# USB_HUB_2_0.net
KiCad netlist of a schematic drawn in Altium Designer
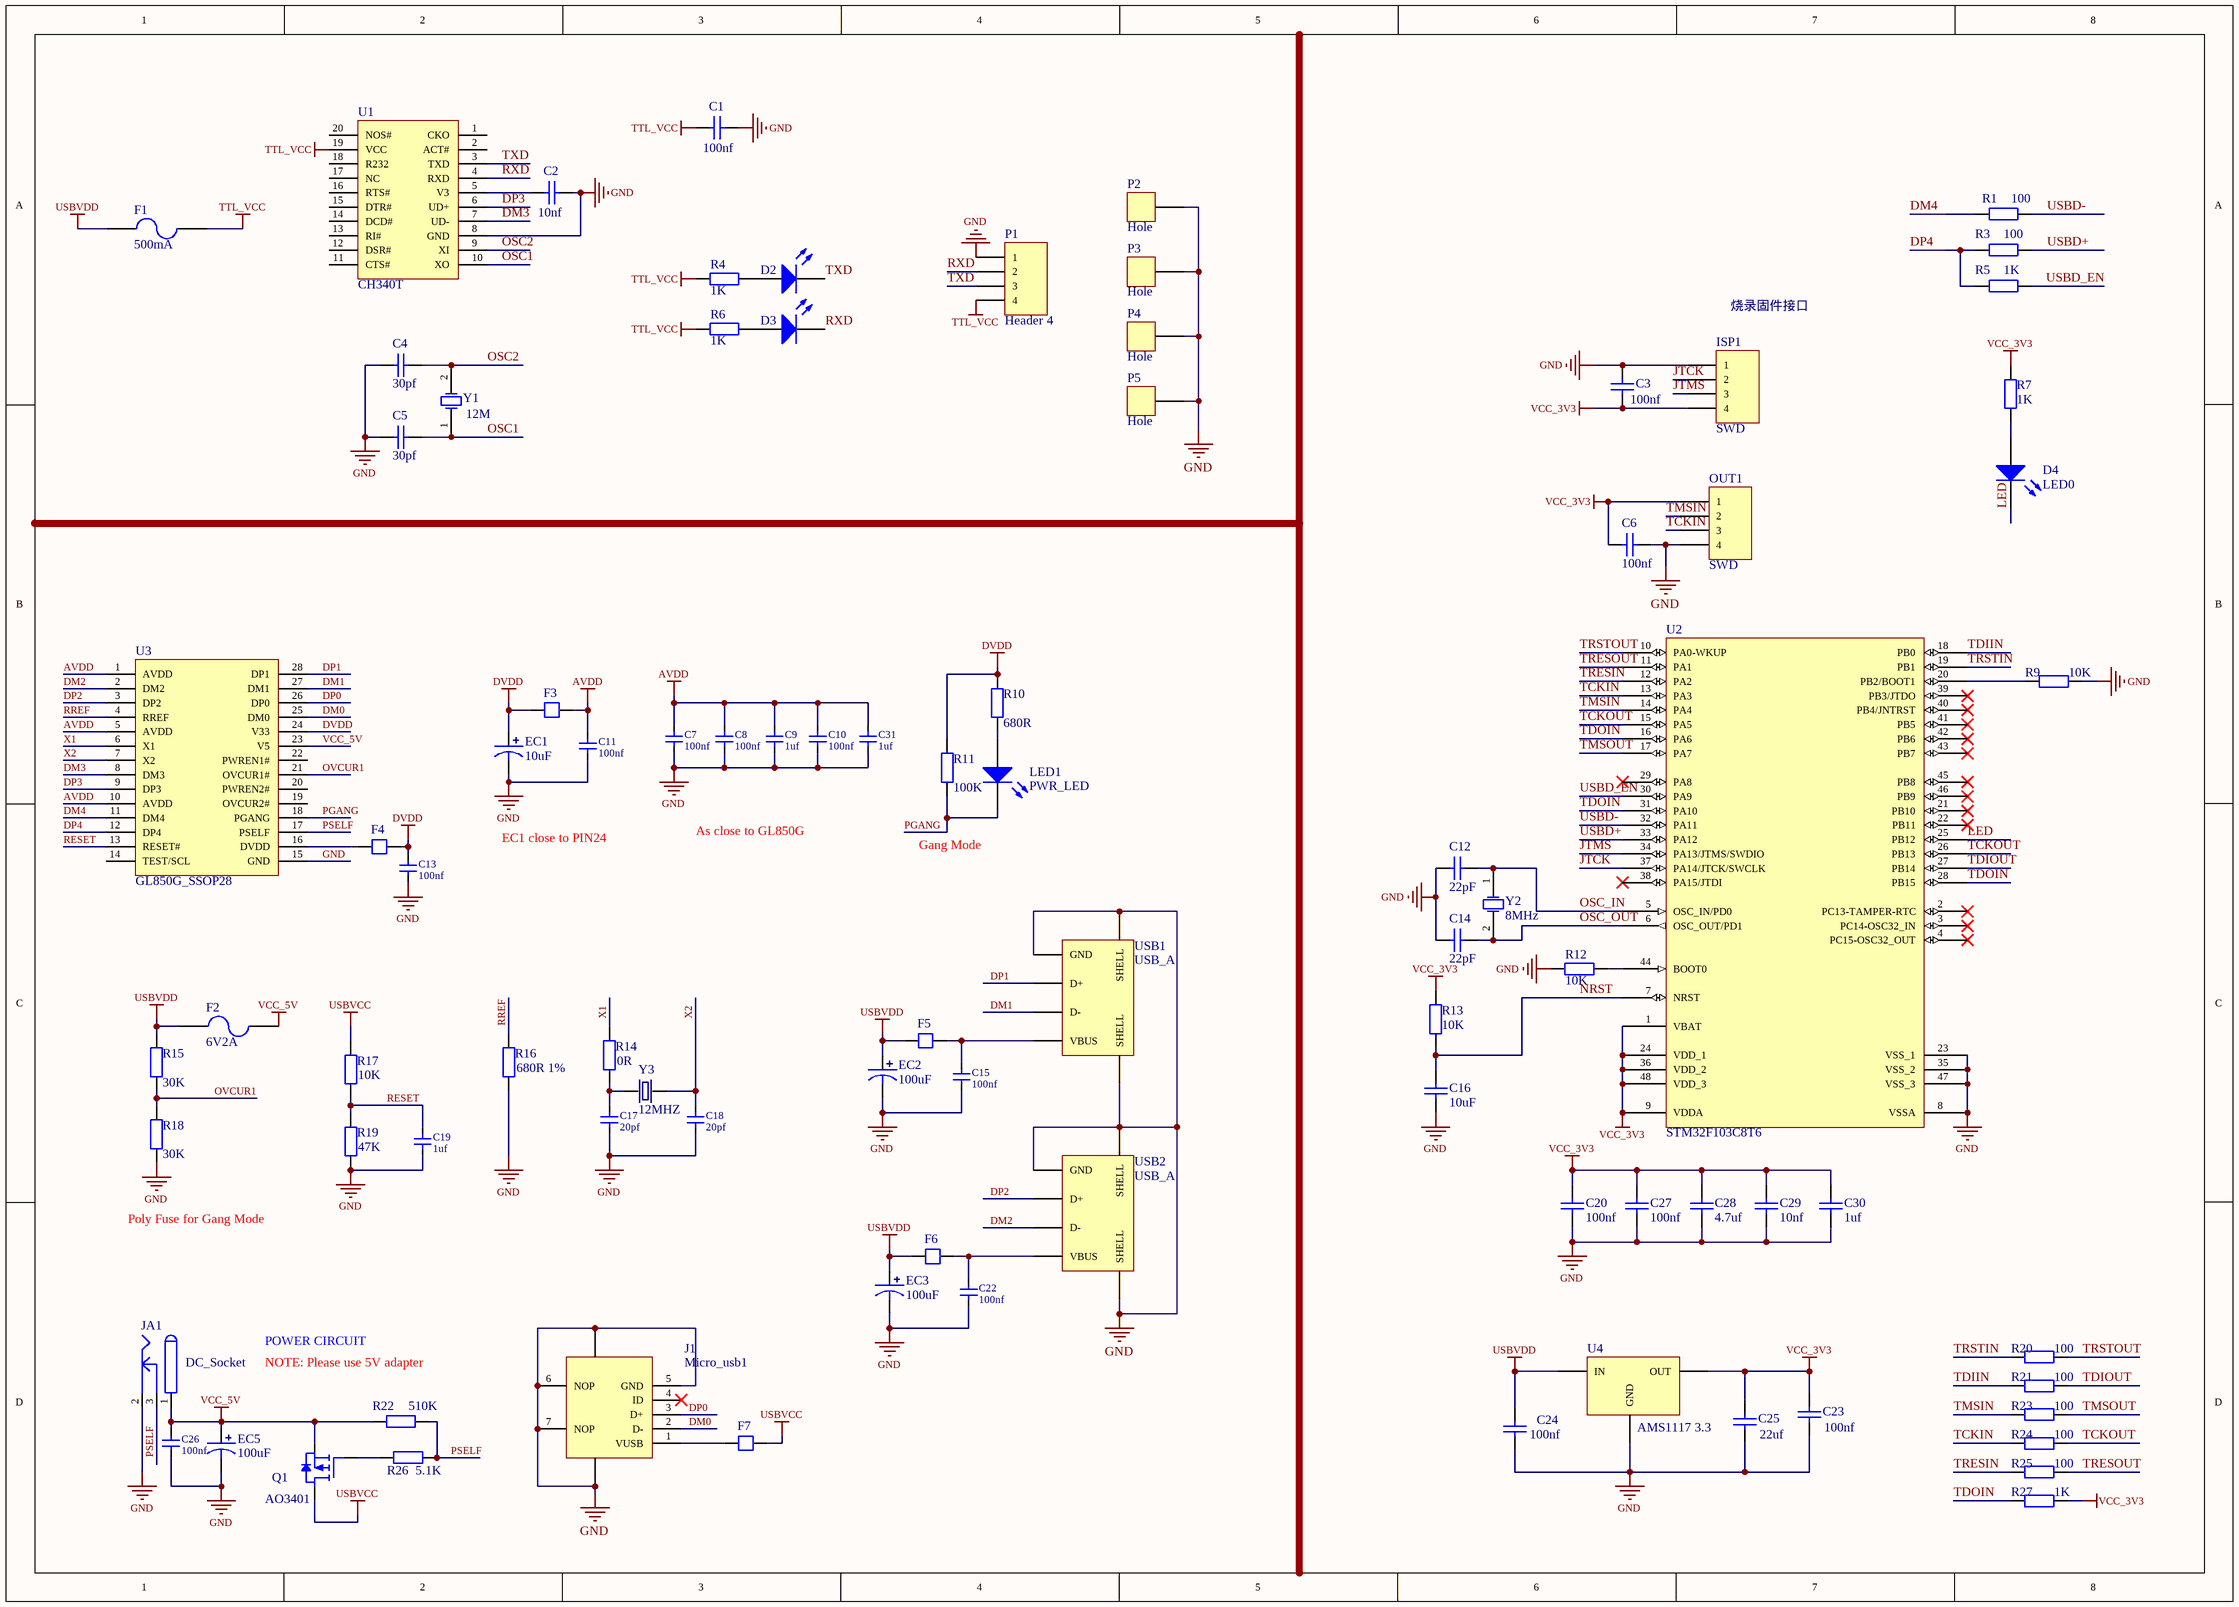
[diagram p0: USB HUB 2.0.SchDoc]

(export (version "E")
  (design (tool "Eeschema 10.0.6"))
  (components
    (comp (ref "C1")
      (value "100nf")
      (footprint "j1-0603")
      (description "Capacitor")
      (fields (field (name "Comment") "Cap") (field (name "PUBLISHER") "Altium Limited"))
      (libsource (lib "Miscellaneous Devices") (part "Cap"))
    )
    (comp (ref "C2")
      (value "10nf")
      (footprint "j1-0603")
      (description "Capacitor")
      (fields (field (name "Comment") "Cap") (field (name "PUBLISHER") "Altium Limited"))
      (libsource (lib "Miscellaneous Devices") (part "Cap"))
    )
    (comp (ref "C3")
      (value "100nf")
      (footprint "j1-0603")
      (description "Capacitor")
      (fields (field (name "PUBLISHER") "Altium Limited"))
      (libsource (lib "Miscellaneous Devices") (part "Cap"))
    )
    (comp (ref "C4")
      (value "30pf")
      (footprint "j1-0603")
      (description "Capacitor")
      (fields (field (name "Comment") "Cap") (field (name "PUBLISHER") "Altium Limited"))
      (libsource (lib "Miscellaneous Devices") (part "Cap"))
    )
    (comp (ref "C5")
      (value "30pf")
      (footprint "j1-0603")
      (description "Capacitor")
      (fields (field (name "Comment") "Cap") (field (name "PUBLISHER") "Altium Limited"))
      (libsource (lib "Miscellaneous Devices") (part "Cap"))
    )
    (comp (ref "C6")
      (value "100nf")
      (footprint "j1-0603")
      (description "Capacitor")
      (fields (field (name "PUBLISHER") "Altium Limited"))
      (libsource (lib "Miscellaneous Devices") (part "Cap"))
    )
    (comp (ref "C7")
      (value "100nf")
      (footprint "j1-0603")
      (description "Capacitor")
      (libsource (lib "Miscellaneous Devices") (part "CAP"))
    )
    (comp (ref "C8")
      (value "100nf")
      (footprint "j1-0603")
      (description "Capacitor")
      (libsource (lib "Miscellaneous Devices") (part "CAP"))
    )
    (comp (ref "C9")
      (value "1uf")
      (footprint "j1-0603")
      (description "Capacitor")
      (libsource (lib "Miscellaneous Devices") (part "CAP"))
    )
    (comp (ref "C10")
      (value "100nf")
      (footprint "j1-0603")
      (description "Capacitor")
      (libsource (lib "Miscellaneous Devices") (part "CAP"))
    )
    (comp (ref "C11")
      (value "100nf")
      (footprint "j1-0603")
      (description "Capacitor")
      (libsource (lib "Miscellaneous Devices") (part "CAP"))
    )
    (comp (ref "C12")
      (value "22pF")
      (footprint "j1-0603")
      (description "Capacitor")
      (fields (field (name "PUBLISHER") "Altium Limited"))
      (libsource (lib "Miscellaneous Devices") (part "Cap"))
    )
    (comp (ref "C13")
      (value "100nf")
      (footprint "j1-0603")
      (description "Capacitor")
      (libsource (lib "Miscellaneous Devices") (part "CAP"))
    )
    (comp (ref "C14")
      (value "22pF")
      (footprint "j1-0603")
      (description "Capacitor")
      (fields (field (name "PUBLISHER") "Altium Limited"))
      (libsource (lib "Miscellaneous Devices") (part "Cap"))
    )
    (comp (ref "C15")
      (value "100nf")
      (footprint "j1-0603")
      (description "Capacitor")
      (libsource (lib "Miscellaneous Devices") (part "CAP"))
    )
    (comp (ref "C16")
      (value "10uF")
      (footprint "j1-0603")
      (description "Capacitor")
      (fields (field (name "PUBLISHER") "Altium Limited"))
      (libsource (lib "Miscellaneous Devices") (part "Cap"))
    )
    (comp (ref "C17")
      (value "20pf")
      (footprint "j1-0603")
      (description "Capacitor")
      (libsource (lib "Miscellaneous Devices") (part "CAP"))
    )
    (comp (ref "C18")
      (value "20pf")
      (footprint "j1-0603")
      (description "Capacitor")
      (libsource (lib "Miscellaneous Devices") (part "CAP"))
    )
    (comp (ref "C19")
      (value "1uf")
      (footprint "j1-0603")
      (description "Capacitor")
      (libsource (lib "Miscellaneous Devices") (part "CAP"))
    )
    (comp (ref "C20")
      (value "100nf")
      (footprint "j1-0603")
      (description "Capacitor")
      (fields (field (name "PUBLISHER") "Altium Limited"))
      (libsource (lib "Miscellaneous Devices") (part "Cap"))
    )
    (comp (ref "C22")
      (value "100nf")
      (footprint "j1-0603")
      (description "Capacitor")
      (libsource (lib "Miscellaneous Devices") (part "CAP"))
    )
    (comp (ref "C23")
      (value "100nf")
      (footprint "j1-0603")
      (description "Capacitor")
      (fields (field (name "PUBLISHER") "Altium Limited"))
      (libsource (lib "Miscellaneous Devices") (part "Cap"))
    )
    (comp (ref "C24")
      (value "100nf")
      (footprint "j1-0603")
      (description "Capacitor")
      (fields (field (name "PUBLISHER") "Altium Limited"))
      (libsource (lib "Miscellaneous Devices") (part "Cap"))
    )
    (comp (ref "C25")
      (value "22uf")
      (footprint "j1-0603")
      (description "Capacitor")
      (fields (field (name "PUBLISHER") "Altium Limited"))
      (libsource (lib "Miscellaneous Devices") (part "Cap"))
    )
    (comp (ref "C26")
      (value "100nf")
      (footprint "j1-0603")
      (description "Capacitor")
      (libsource (lib "Miscellaneous Devices") (part "CAP"))
    )
    (comp (ref "C27")
      (value "100nf")
      (footprint "j1-0603")
      (description "Capacitor")
      (fields (field (name "PUBLISHER") "Altium Limited"))
      (libsource (lib "Miscellaneous Devices") (part "Cap"))
    )
    (comp (ref "C28")
      (value "4.7uf")
      (footprint "j1-0603")
      (description "Capacitor")
      (fields (field (name "PUBLISHER") "Altium Limited"))
      (libsource (lib "Miscellaneous Devices") (part "Cap"))
    )
    (comp (ref "C29")
      (value "10nf")
      (footprint "j1-0603")
      (description "Capacitor")
      (fields (field (name "PUBLISHER") "Altium Limited"))
      (libsource (lib "Miscellaneous Devices") (part "Cap"))
    )
    (comp (ref "C30")
      (value "1uf")
      (footprint "j1-0603")
      (description "Capacitor")
      (fields (field (name "PUBLISHER") "Altium Limited"))
      (libsource (lib "Miscellaneous Devices") (part "Cap"))
    )
    (comp (ref "C31")
      (value "1uf")
      (footprint "j1-0603")
      (description "Capacitor")
      (libsource (lib "Miscellaneous Devices") (part "CAP"))
    )
    (comp (ref "D2")
      (value "LED")
      (footprint "j1-0603")
      (description "Typical INFRARED GaAs LED")
      (fields (field (name "PUBLISHER") "Altium Limited"))
      (libsource (lib "Miscellaneous Devices") (part "LED0"))
    )
    (comp (ref "D3")
      (value "LED")
      (footprint "j1-0603")
      (description "Typical INFRARED GaAs LED")
      (fields (field (name "PUBLISHER") "Altium Limited"))
      (libsource (lib "Miscellaneous Devices") (part "LED0"))
    )
    (comp (ref "D4")
      (value "LED0")
      (footprint "j1-0603")
      (description "Typical INFRARED GaAs LED")
      (fields (field (name "PUBLISHER") "Altium Limited"))
      (libsource (lib "Miscellaneous Devices") (part "LED0"))
    )
    (comp (ref "EC1")
      (value "10uF")
      (footprint "6-0805_L")
      (description "贴片电解电容")
      (libsource (lib "电容") (part "SMD_ECAP"))
    )
    (comp (ref "EC2")
      (value "100uF")
      (footprint "SMD-EC5.0X5.3X5.4")
      (description "贴片电解电容")
      (libsource (lib "电容") (part "SMD_ECAP"))
    )
    (comp (ref "EC3")
      (value "100uF")
      (footprint "SMD-EC5.0X5.3X5.4")
      (description "贴片电解电容")
      (libsource (lib "电容") (part "SMD_ECAP"))
    )
    (comp (ref "EC5")
      (value "100uF")
      (footprint "SMD-EC5.0X5.3X5.4")
      (description "贴片电解电容")
      (libsource (lib "电容") (part "SMD_ECAP"))
    )
    (comp (ref "F1")
      (value "500mA")
      (footprint "1812C")
      (description "Fuse")
      (fields (field (name "PUBLISHER") "Altium Limited"))
      (libsource (lib "Miscellaneous Devices") (part "Fuse 2"))
    )
    (comp (ref "F2")
      (value "6V2A")
      (footprint "1812")
      (description "Fuse")
      (fields (field (name "PUBLISHER") "Altium Limited"))
      (libsource (lib "Miscellaneous Devices") (part "Fuse 2"))
    )
    (comp (ref "F3") (value "FB") (footprint "6-0805_L") (libsource (lib "haoxaingyin") (part "FB")))
    (comp (ref "F4") (value "FB") (footprint "6-0805_L") (libsource (lib "haoxaingyin") (part "FB")))
    (comp (ref "F5") (value "FB") (footprint "6-0805_L") (libsource (lib "haoxaingyin") (part "FB")))
    (comp (ref "F6") (value "FB") (footprint "6-0805_L") (libsource (lib "haoxaingyin") (part "FB")))
    (comp (ref "F7") (value "FB") (footprint "6-0805_L") (libsource (lib "haoxaingyin") (part "FB")))
    (comp (ref "ISP1")
      (value "SWD")
      (footprint "HDR1X4")
      (description "Header, 4-Pin")
      (fields (field (name "PUBLISHER") "Altium Limited"))
      (libsource (lib "Miscellaneous Connectors") (part "Header 4"))
    )
    (comp (ref "J1")
      (value "Micro_usb1")
      (footprint "Micro_USB1")
      (libsource (lib "haoxaingyin") (part "Micro_usb1"))
    )
    (comp (ref "JA1") (value "DC_Socket") (footprint "DC-002") (libsource (lib "电源插座") (part "DC_Socket")))
    (comp (ref "LED1")
      (value "PWR_LED")
      (footprint "j1-0603")
      (description "Typical INFRARED GaAs LED")
      (fields (field (name "PUBLISHER") "Altium Limited"))
      (libsource (lib "Miscellaneous Devices") (part "LED0"))
    )
    (comp (ref "OUT1")
      (value "SWD")
      (footprint "HDR1X4")
      (description "Header, 4-Pin")
      (fields (field (name "PUBLISHER") "Altium Limited"))
      (libsource (lib "Miscellaneous Connectors") (part "Header 4"))
    )
    (comp (ref "P1")
      (value "Header 4")
      (footprint "HDR1X4")
      (description "Header, 4-Pin")
      (fields (field (name "PUBLISHER") "Altium Limited"))
      (libsource (lib "Connectors") (part "Header 4"))
    )
    (comp (ref "P2") (value "Hole") (footprint "Hole") (libsource (lib "haoxaingyin") (part "Hole")))
    (comp (ref "P3") (value "Hole") (footprint "Hole") (libsource (lib "haoxaingyin") (part "Hole")))
    (comp (ref "P4") (value "Hole") (footprint "Hole") (libsource (lib "haoxaingyin") (part "Hole")))
    (comp (ref "P5") (value "Hole") (footprint "Hole") (libsource (lib "haoxaingyin") (part "Hole")))
    (comp (ref "Q1")
      (value "AO3401")
      (footprint "SOT-23")
      (description "P-Channel MOSFET")
      (libsource (lib "Miscellaneous Devices") (part "MOSFET-P"))
    )
    (comp (ref "R1")
      (value "100")
      (footprint "j1-0603")
      (description "Resistor")
      (fields (field (name "PUBLISHER") "Altium Limited"))
      (libsource (lib "") (part "Res2_1"))
    )
    (comp (ref "R3")
      (value "100")
      (footprint "j1-0603")
      (description "Resistor")
      (fields (field (name "PUBLISHER") "Altium Limited"))
      (libsource (lib "") (part "Res2_1"))
    )
    (comp (ref "R4")
      (value "1K")
      (footprint "j1-0603")
      (description "Resistor")
      (fields (field (name "Comment") "Res2") (field (name "PUBLISHER") "Altium Limited"))
      (libsource (lib "") (part "Res2_1"))
    )
    (comp (ref "R5")
      (value "1K")
      (footprint "j1-0603")
      (description "Resistor")
      (fields (field (name "PUBLISHER") "Altium Limited"))
      (libsource (lib "") (part "Res2_1"))
    )
    (comp (ref "R6")
      (value "1K")
      (footprint "j1-0603")
      (description "Resistor")
      (fields (field (name "Comment") "Res2") (field (name "PUBLISHER") "Altium Limited"))
      (libsource (lib "") (part "Res2_1"))
    )
    (comp (ref "R7")
      (value "1K")
      (footprint "j1-0603")
      (description "Resistor")
      (fields (field (name "PUBLISHER") "Altium Limited"))
      (libsource (lib "Miscellaneous Devices") (part "Res2"))
    )
    (comp (ref "R9")
      (value "10K")
      (footprint "j1-0603")
      (description "Resistor")
      (fields (field (name "PUBLISHER") "Altium Limited"))
      (libsource (lib "") (part "Res2_1"))
    )
    (comp (ref "R10")
      (value "680R")
      (footprint "j1-0603")
      (description "Resistor")
      (fields (field (name "PUBLISHER") "Altium Limited"))
      (libsource (lib "Miscellaneous Devices") (part "Res2"))
    )
    (comp (ref "R11")
      (value "100K")
      (footprint "j1-0603")
      (description "Resistor")
      (fields (field (name "PUBLISHER") "Altium Limited"))
      (libsource (lib "Miscellaneous Devices") (part "Res2"))
    )
    (comp (ref "R12")
      (value "10K")
      (footprint "j1-0603")
      (description "Resistor")
      (fields (field (name "PUBLISHER") "Altium Limited"))
      (libsource (lib "") (part "Res2_1"))
    )
    (comp (ref "R13")
      (value "10K")
      (footprint "j1-0603")
      (description "Resistor")
      (fields (field (name "PUBLISHER") "Altium Limited"))
      (libsource (lib "Miscellaneous Devices") (part "Res2"))
    )
    (comp (ref "R14")
      (value "0R")
      (footprint "j1-0603")
      (description "Resistor")
      (fields (field (name "PUBLISHER") "Altium Limited"))
      (libsource (lib "Miscellaneous Devices") (part "Res2"))
    )
    (comp (ref "R15")
      (value "30K")
      (footprint "j1-0603")
      (description "Resistor")
      (fields (field (name "PUBLISHER") "Altium Limited"))
      (libsource (lib "Miscellaneous Devices") (part "Res2"))
    )
    (comp (ref "R16")
      (value "680R 1%")
      (footprint "j1-0603")
      (description "Resistor")
      (fields (field (name "PUBLISHER") "Altium Limited"))
      (libsource (lib "Miscellaneous Devices") (part "Res2"))
    )
    (comp (ref "R17")
      (value "10K")
      (footprint "j1-0603")
      (description "Resistor")
      (fields (field (name "PUBLISHER") "Altium Limited"))
      (libsource (lib "Miscellaneous Devices") (part "Res2"))
    )
    (comp (ref "R18")
      (value "30K")
      (footprint "j1-0603")
      (description "Resistor")
      (fields (field (name "PUBLISHER") "Altium Limited"))
      (libsource (lib "Miscellaneous Devices") (part "Res2"))
    )
    (comp (ref "R19")
      (value "47K")
      (footprint "j1-0603")
      (description "Resistor")
      (fields (field (name "PUBLISHER") "Altium Limited"))
      (libsource (lib "Miscellaneous Devices") (part "Res2"))
    )
    (comp (ref "R20")
      (value "100")
      (footprint "j1-0603")
      (description "Resistor")
      (fields (field (name "PUBLISHER") "Altium Limited"))
      (libsource (lib "") (part "Res2_1"))
    )
    (comp (ref "R21")
      (value "100")
      (footprint "j1-0603")
      (description "Resistor")
      (fields (field (name "PUBLISHER") "Altium Limited"))
      (libsource (lib "") (part "Res2_1"))
    )
    (comp (ref "R22")
      (value "510K")
      (footprint "j1-0603")
      (description "Resistor")
      (fields (field (name "PUBLISHER") "Altium Limited"))
      (libsource (lib "") (part "Res2_2"))
    )
    (comp (ref "R23")
      (value "100")
      (footprint "j1-0603")
      (description "Resistor")
      (fields (field (name "PUBLISHER") "Altium Limited"))
      (libsource (lib "") (part "Res2_1"))
    )
    (comp (ref "R24")
      (value "100")
      (footprint "j1-0603")
      (description "Resistor")
      (fields (field (name "PUBLISHER") "Altium Limited"))
      (libsource (lib "") (part "Res2_1"))
    )
    (comp (ref "R25")
      (value "100")
      (footprint "j1-0603")
      (description "Resistor")
      (fields (field (name "PUBLISHER") "Altium Limited"))
      (libsource (lib "") (part "Res2_1"))
    )
    (comp (ref "R26")
      (value "5.1K")
      (footprint "j1-0603")
      (description "Resistor")
      (fields (field (name "PUBLISHER") "Altium Limited"))
      (libsource (lib "") (part "Res2_1"))
    )
    (comp (ref "R27")
      (value "1K")
      (footprint "j1-0603")
      (description "Resistor")
      (fields (field (name "PUBLISHER") "Altium Limited"))
      (libsource (lib "") (part "Res2_1"))
    )
    (comp (ref "U1") (value "CH340T") (footprint "SSOP20") (libsource (lib "haoxaingyin") (part "CH340T")))
    (comp (ref "U2")
      (value "STM32F103C8T6")
      (footprint "LQFP48 7X7")
      (libsource (lib "STM32系列") (part "STM32F103C8T6"))
    )
    (comp (ref "U3")
      (value "GL850G_SSOP28")
      (footprint "SSOP28")
      (libsource (lib "haoxaingyin") (part "GL850G_SSOP28"))
    )
    (comp (ref "U4")
      (value "AMS1117 3.3")
      (footprint "SOT-223")
      (libsource (lib "Common Power") (part "ASM1117"))
    )
    (comp (ref "USB1") (value "USB_A") (footprint "USB_DIP") (libsource (lib "haoxaingyin") (part "USB_A")))
    (comp (ref "USB2") (value "USB_A") (footprint "USB_DIP") (libsource (lib "haoxaingyin") (part "USB_A")))
    (comp (ref "Y1")
      (value "12M")
      (footprint "HC-49/U-S")
      (description "Crystal Oscillator")
      (fields (field (name "PUBLISHER") "Altium Limited"))
      (libsource (lib "Common Device") (part "XTAL"))
    )
    (comp (ref "Y2")
      (value "8MHz")
      (footprint "HC-49/U-S")
      (description "Crystal Oscillator")
      (fields (field (name "PUBLISHER") "Altium Limited"))
      (libsource (lib "Miscellaneous Devices") (part "XTAL"))
    )
    (comp (ref "Y3") (value "12MHZ") (footprint "HC-49/U-S") (libsource (lib "Common Device") (part "Xtal")))
  )
  (nets
    (net (code "1") (name "/DM0") (class "Default")
      (node (ref "J1") (pin "2") (pinfunction "D-_2") (pintype "passive"))
      (node (ref "U3") (pin "25") (pinfunction "DM0_25") (pintype "passive"))
    )
    (net (code "2") (name "/DM1") (class "Default")
      (node (ref "U3") (pin "27") (pinfunction "DM1_27") (pintype "passive"))
      (node (ref "USB1") (pin "2") (pinfunction "D-_2") (pintype "passive"))
    )
    (net (code "3") (name "/DM2") (class "Default")
      (node (ref "U3") (pin "2") (pinfunction "DM2_2") (pintype "passive"))
      (node (ref "USB2") (pin "2") (pinfunction "D-_2") (pintype "passive"))
    )
    (net (code "4") (name "/DM3") (class "Default")
      (node (ref "U1") (pin "7") (pinfunction "UD-_7") (pintype "passive"))
      (node (ref "U3") (pin "8") (pinfunction "DM3_8") (pintype "passive"))
    )
    (net (code "5") (name "/DM4") (class "Default")
      (node (ref "R1") (pin "1") (pinfunction "1_1") (pintype "passive"))
      (node (ref "U3") (pin "11") (pinfunction "DM4_11") (pintype "passive"))
    )
    (net (code "6") (name "/DP0") (class "Default")
      (node (ref "J1") (pin "3") (pinfunction "D+_3") (pintype "passive"))
      (node (ref "U3") (pin "26") (pinfunction "DP0_26") (pintype "passive"))
    )
    (net (code "7") (name "/DP1") (class "Default")
      (node (ref "U3") (pin "28") (pinfunction "DP1_28") (pintype "passive"))
      (node (ref "USB1") (pin "3") (pinfunction "D+_3") (pintype "passive"))
    )
    (net (code "8") (name "/DP2") (class "Default")
      (node (ref "U3") (pin "3") (pinfunction "DP2_3") (pintype "passive"))
      (node (ref "USB2") (pin "3") (pinfunction "D+_3") (pintype "passive"))
    )
    (net (code "9") (name "/DP3") (class "Default")
      (node (ref "U1") (pin "6") (pinfunction "UD+_6") (pintype "passive"))
      (node (ref "U3") (pin "9") (pinfunction "DP3_9") (pintype "passive"))
    )
    (net (code "10") (name "/DP4") (class "Default")
      (node (ref "R3") (pin "1") (pinfunction "1_1") (pintype "passive"))
      (node (ref "R5") (pin "1") (pinfunction "1_1") (pintype "passive"))
      (node (ref "U3") (pin "12") (pinfunction "DP4_12") (pintype "passive"))
    )
    (net (code "11") (name "/JTCK") (class "Default")
      (node (ref "ISP1") (pin "2") (pinfunction "2_2") (pintype "passive"))
      (node (ref "U2") (pin "37") (pinfunction "PA14/JTCK/SWCLK_37") (pintype "bidirectional"))
    )
    (net (code "12") (name "/JTMS") (class "Default")
      (node (ref "ISP1") (pin "3") (pinfunction "3_3") (pintype "passive"))
      (node (ref "U2") (pin "34") (pinfunction "PA13/JTMS/SWDIO_34") (pintype "bidirectional"))
    )
    (net (code "13") (name "/LED") (class "Default")
      (node (ref "D4") (pin "2") (pinfunction "2_2") (pintype "passive"))
      (node (ref "U2") (pin "25") (pinfunction "PB12_25") (pintype "bidirectional"))
    )
    (net (code "14") (name "/NRST") (class "Default")
      (node (ref "C16") (pin "1") (pinfunction "1_1") (pintype "passive"))
      (node (ref "R13") (pin "1") (pinfunction "1_1") (pintype "passive"))
      (node (ref "U2") (pin "7") (pinfunction "NRST_7") (pintype "bidirectional"))
    )
    (net (code "15") (name "/OSC1") (class "Default")
      (node (ref "C5") (pin "1") (pinfunction "1_1") (pintype "passive"))
      (node (ref "U1") (pin "10") (pinfunction "XO_10") (pintype "passive"))
      (node (ref "Y1") (pin "1") (pinfunction "OSC1_1") (pintype "passive"))
    )
    (net (code "16") (name "/OSC2") (class "Default")
      (node (ref "C4") (pin "1") (pinfunction "1_1") (pintype "passive"))
      (node (ref "U1") (pin "9") (pinfunction "XI_9") (pintype "passive"))
      (node (ref "Y1") (pin "2") (pinfunction "OSC2_2") (pintype "passive"))
    )
    (net (code "17") (name "/OSC_IN") (class "Default")
      (node (ref "C12") (pin "1") (pinfunction "1_1") (pintype "passive"))
      (node (ref "U2") (pin "5") (pinfunction "OSC_IN/PD0_5") (pintype "input"))
      (node (ref "Y2") (pin "1") (pinfunction "OSC1_1") (pintype "passive"))
    )
    (net (code "18") (name "/OSC_OUT") (class "Default")
      (node (ref "C14") (pin "1") (pinfunction "1_1") (pintype "passive"))
      (node (ref "U2") (pin "6") (pinfunction "OSC_OUT/PD1_6") (pintype "output"))
      (node (ref "Y2") (pin "2") (pinfunction "OSC2_2") (pintype "passive"))
    )
    (net (code "19") (name "/OVCUR1") (class "Default")
      (node (ref "R15") (pin "1") (pinfunction "1_1") (pintype "passive"))
      (node (ref "R18") (pin "2") (pinfunction "2_2") (pintype "passive"))
      (node (ref "U3") (pin "21") (pinfunction "OVCUR1#_21") (pintype "passive"))
    )
    (net (code "20") (name "/PGANG") (class "Default")
      (node (ref "LED1") (pin "2") (pinfunction "2_2") (pintype "passive"))
      (node (ref "R11") (pin "1") (pinfunction "1_1") (pintype "passive"))
      (node (ref "U3") (pin "18") (pinfunction "PGANG_18") (pintype "passive"))
    )
    (net (code "21") (name "/PSELF") (class "Default")
      (node (ref "JA1") (pin "3") (pinfunction "3_3") (pintype "power_in"))
      (node (ref "R22") (pin "1") (pinfunction "1_1") (pintype "passive"))
      (node (ref "R26") (pin "2") (pinfunction "2_2") (pintype "passive"))
      (node (ref "U3") (pin "17") (pinfunction "PSELF_17") (pintype "passive"))
    )
    (net (code "22") (name "/RESET") (class "Default")
      (node (ref "C19") (pin "2") (pinfunction "2_2") (pintype "passive"))
      (node (ref "R17") (pin "1") (pinfunction "1_1") (pintype "passive"))
      (node (ref "R19") (pin "2") (pinfunction "2_2") (pintype "passive"))
      (node (ref "U3") (pin "13") (pinfunction "RESET#_13") (pintype "passive"))
    )
    (net (code "23") (name "/RREF") (class "Default")
      (node (ref "R16") (pin "2") (pinfunction "2_2") (pintype "passive"))
      (node (ref "U3") (pin "4") (pinfunction "RREF_4") (pintype "passive"))
    )
    (net (code "24") (name "/RXD") (class "Default")
      (node (ref "D3") (pin "2") (pinfunction "2_2") (pintype "passive"))
      (node (ref "P1") (pin "2") (pinfunction "2_2") (pintype "passive"))
      (node (ref "U1") (pin "4") (pinfunction "RXD_4") (pintype "passive"))
    )
    (net (code "25") (name "/TCKIN") (class "Default")
      (node (ref "OUT1") (pin "3") (pinfunction "3_3") (pintype "passive"))
      (node (ref "R24") (pin "1") (pinfunction "1_1") (pintype "passive"))
      (node (ref "U2") (pin "13") (pinfunction "PA3_13") (pintype "bidirectional"))
    )
    (net (code "26") (name "/TCKOUT") (class "Default")
      (node (ref "R24") (pin "2") (pinfunction "2_2") (pintype "passive"))
      (node (ref "U2") (pin "15") (pinfunction "PA5_15") (pintype "bidirectional"))
      (node (ref "U2") (pin "26") (pinfunction "PB13_26") (pintype "bidirectional"))
    )
    (net (code "27") (name "/TDIIN") (class "Default")
      (node (ref "R21") (pin "1") (pinfunction "1_1") (pintype "passive"))
      (node (ref "U2") (pin "18") (pinfunction "PB0_18") (pintype "bidirectional"))
    )
    (net (code "28") (name "/TDIOUT") (class "Default")
      (node (ref "R21") (pin "2") (pinfunction "2_2") (pintype "passive"))
      (node (ref "U2") (pin "27") (pinfunction "PB14_27") (pintype "bidirectional"))
    )
    (net (code "29") (name "/TDOIN") (class "Default")
      (node (ref "R27") (pin "1") (pinfunction "1_1") (pintype "passive"))
      (node (ref "U2") (pin "16") (pinfunction "PA6_16") (pintype "bidirectional"))
      (node (ref "U2") (pin "28") (pinfunction "PB15_28") (pintype "bidirectional"))
      (node (ref "U2") (pin "31") (pinfunction "PA10_31") (pintype "bidirectional"))
    )
    (net (code "30") (name "/TMSIN") (class "Default")
      (node (ref "OUT1") (pin "2") (pinfunction "2_2") (pintype "passive"))
      (node (ref "R23") (pin "1") (pinfunction "1_1") (pintype "passive"))
      (node (ref "U2") (pin "14") (pinfunction "PA4_14") (pintype "bidirectional"))
    )
    (net (code "31") (name "/TMSOUT") (class "Default")
      (node (ref "R23") (pin "2") (pinfunction "2_2") (pintype "passive"))
      (node (ref "U2") (pin "17") (pinfunction "PA7_17") (pintype "bidirectional"))
    )
    (net (code "32") (name "/TRESIN") (class "Default")
      (node (ref "R25") (pin "1") (pinfunction "1_1") (pintype "passive"))
      (node (ref "U2") (pin "12") (pinfunction "PA2_12") (pintype "bidirectional"))
    )
    (net (code "33") (name "/TRESOUT") (class "Default")
      (node (ref "R25") (pin "2") (pinfunction "2_2") (pintype "passive"))
      (node (ref "U2") (pin "11") (pinfunction "PA1_11") (pintype "bidirectional"))
    )
    (net (code "34") (name "/TRSTIN") (class "Default")
      (node (ref "R20") (pin "1") (pinfunction "1_1") (pintype "passive"))
      (node (ref "U2") (pin "19") (pinfunction "PB1_19") (pintype "bidirectional"))
    )
    (net (code "35") (name "/TRSTOUT") (class "Default")
      (node (ref "R20") (pin "2") (pinfunction "2_2") (pintype "passive"))
      (node (ref "U2") (pin "10") (pinfunction "PA0-WKUP_10") (pintype "bidirectional"))
    )
    (net (code "36") (name "/TXD") (class "Default")
      (node (ref "D2") (pin "2") (pinfunction "2_2") (pintype "passive"))
      (node (ref "P1") (pin "3") (pinfunction "3_3") (pintype "passive"))
      (node (ref "U1") (pin "3") (pinfunction "TXD_3") (pintype "passive"))
    )
    (net (code "37") (name "/USBD+") (class "Default")
      (node (ref "R3") (pin "2") (pinfunction "2_2") (pintype "passive"))
      (node (ref "U2") (pin "33") (pinfunction "PA12_33") (pintype "bidirectional"))
    )
    (net (code "38") (name "/USBD-") (class "Default")
      (node (ref "R1") (pin "2") (pinfunction "2_2") (pintype "passive"))
      (node (ref "U2") (pin "32") (pinfunction "PA11_32") (pintype "bidirectional"))
    )
    (net (code "39") (name "/USBD_EN") (class "Default")
      (node (ref "R5") (pin "2") (pinfunction "2_2") (pintype "passive"))
      (node (ref "U2") (pin "30") (pinfunction "PA9_30") (pintype "bidirectional"))
    )
    (net (code "40") (name "/X1") (class "Default")
      (node (ref "R14") (pin "2") (pinfunction "2_2") (pintype "passive"))
      (node (ref "U3") (pin "6") (pinfunction "X1_6") (pintype "passive"))
    )
    (net (code "41") (name "/X2") (class "Default")
      (node (ref "C18") (pin "2") (pinfunction "2_2") (pintype "passive"))
      (node (ref "U3") (pin "7") (pinfunction "X2_7") (pintype "passive"))
      (node (ref "Y3") (pin "2") (pinfunction "1_2") (pintype "passive"))
    )
    (net (code "42") (name "AVDD") (class "Default")
      (node (ref "C10") (pin "2") (pinfunction "2_2") (pintype "passive"))
      (node (ref "C11") (pin "2") (pinfunction "2_2") (pintype "passive"))
      (node (ref "C31") (pin "2") (pinfunction "2_2") (pintype "passive"))
      (node (ref "C7") (pin "2") (pinfunction "2_2") (pintype "passive"))
      (node (ref "C8") (pin "2") (pinfunction "2_2") (pintype "passive"))
      (node (ref "C9") (pin "2") (pinfunction "2_2") (pintype "passive"))
      (node (ref "F3") (pin "2") (pinfunction "2_2") (pintype "passive"))
      (node (ref "U3") (pin "1") (pinfunction "AVDD_1") (pintype "passive"))
      (node (ref "U3") (pin "10") (pinfunction "AVDD_10") (pintype "passive"))
      (node (ref "U3") (pin "5") (pinfunction "AVDD_5") (pintype "passive"))
    )
    (net (code "43") (name "DVDD") (class "Default")
      (node (ref "C13") (pin "2") (pinfunction "2_2") (pintype "passive"))
      (node (ref "EC1") (pin "1") (pinfunction "1_1") (pintype "passive"))
      (node (ref "F3") (pin "1") (pinfunction "1_1") (pintype "passive"))
      (node (ref "F4") (pin "2") (pinfunction "2_2") (pintype "passive"))
      (node (ref "R10") (pin "2") (pinfunction "2_2") (pintype "passive"))
      (node (ref "R11") (pin "2") (pinfunction "2_2") (pintype "passive"))
      (node (ref "U3") (pin "24") (pinfunction "V33_24") (pintype "passive"))
    )
    (net (code "44") (name "GND") (class "Default")
      (node (ref "C1") (pin "1") (pinfunction "1_1") (pintype "passive"))
      (node (ref "C10") (pin "1") (pinfunction "1_1") (pintype "passive"))
      (node (ref "C11") (pin "1") (pinfunction "1_1") (pintype "passive"))
      (node (ref "C12") (pin "2") (pinfunction "2_2") (pintype "passive"))
      (node (ref "C13") (pin "1") (pinfunction "1_1") (pintype "passive"))
      (node (ref "C14") (pin "2") (pinfunction "2_2") (pintype "passive"))
      (node (ref "C15") (pin "1") (pinfunction "1_1") (pintype "passive"))
      (node (ref "C16") (pin "2") (pinfunction "2_2") (pintype "passive"))
      (node (ref "C17") (pin "1") (pinfunction "1_1") (pintype "passive"))
      (node (ref "C18") (pin "1") (pinfunction "1_1") (pintype "passive"))
      (node (ref "C19") (pin "1") (pinfunction "1_1") (pintype "passive"))
      (node (ref "C2") (pin "1") (pinfunction "1_1") (pintype "passive"))
      (node (ref "C20") (pin "2") (pinfunction "2_2") (pintype "passive"))
      (node (ref "C22") (pin "1") (pinfunction "1_1") (pintype "passive"))
      (node (ref "C23") (pin "2") (pinfunction "2_2") (pintype "passive"))
      (node (ref "C24") (pin "2") (pinfunction "2_2") (pintype "passive"))
      (node (ref "C25") (pin "2") (pinfunction "2_2") (pintype "passive"))
      (node (ref "C26") (pin "1") (pinfunction "1_1") (pintype "passive"))
      (node (ref "C27") (pin "2") (pinfunction "2_2") (pintype "passive"))
      (node (ref "C28") (pin "2") (pinfunction "2_2") (pintype "passive"))
      (node (ref "C29") (pin "2") (pinfunction "2_2") (pintype "passive"))
      (node (ref "C3") (pin "2") (pinfunction "2_2") (pintype "passive"))
      (node (ref "C30") (pin "2") (pinfunction "2_2") (pintype "passive"))
      (node (ref "C31") (pin "1") (pinfunction "1_1") (pintype "passive"))
      (node (ref "C4") (pin "2") (pinfunction "2_2") (pintype "passive"))
      (node (ref "C5") (pin "2") (pinfunction "2_2") (pintype "passive"))
      (node (ref "C6") (pin "2") (pinfunction "2_2") (pintype "passive"))
      (node (ref "C7") (pin "1") (pinfunction "1_1") (pintype "passive"))
      (node (ref "C8") (pin "1") (pinfunction "1_1") (pintype "passive"))
      (node (ref "C9") (pin "1") (pinfunction "1_1") (pintype "passive"))
      (node (ref "EC1") (pin "2") (pinfunction "2_2") (pintype "passive"))
      (node (ref "EC2") (pin "2") (pinfunction "2_2") (pintype "passive"))
      (node (ref "EC3") (pin "2") (pinfunction "2_2") (pintype "passive"))
      (node (ref "EC5") (pin "2") (pinfunction "2_2") (pintype "passive"))
      (node (ref "ISP1") (pin "1") (pinfunction "1_1") (pintype "passive"))
      (node (ref "J1") (pin "5") (pinfunction "GND_5") (pintype "passive"))
      (node (ref "J1") (pin "6") (pinfunction "NOP_6") (pintype "passive"))
      (node (ref "J1") (pin "7") (pinfunction "NOP_7") (pintype "passive"))
      (node (ref "J1") (pin "8") (pinfunction "8_8") (pintype "passive"))
      (node (ref "J1") (pin "9") (pinfunction "9_9") (pintype "passive"))
      (node (ref "JA1") (pin "2") (pinfunction "2_2") (pintype "power_in"))
      (node (ref "OUT1") (pin "4") (pinfunction "4_4") (pintype "passive"))
      (node (ref "P1") (pin "1") (pinfunction "1_1") (pintype "passive"))
      (node (ref "P2") (pin "1") (pinfunction "1_1") (pintype "passive"))
      (node (ref "P3") (pin "1") (pinfunction "1_1") (pintype "passive"))
      (node (ref "P4") (pin "1") (pinfunction "1_1") (pintype "passive"))
      (node (ref "P5") (pin "1") (pinfunction "1_1") (pintype "passive"))
      (node (ref "R12") (pin "1") (pinfunction "1_1") (pintype "passive"))
      (node (ref "R16") (pin "1") (pinfunction "1_1") (pintype "passive"))
      (node (ref "R18") (pin "1") (pinfunction "1_1") (pintype "passive"))
      (node (ref "R19") (pin "1") (pinfunction "1_1") (pintype "passive"))
      (node (ref "R9") (pin "2") (pinfunction "2_2") (pintype "passive"))
      (node (ref "U1") (pin "8") (pinfunction "GND_8") (pintype "passive"))
      (node (ref "U2") (pin "23") (pinfunction "VSS_1_23") (pintype "power_in"))
      (node (ref "U2") (pin "35") (pinfunction "VSS_2_35") (pintype "power_in"))
      (node (ref "U2") (pin "47") (pinfunction "VSS_3_47") (pintype "power_in"))
      (node (ref "U2") (pin "8") (pinfunction "VSSA_8") (pintype "power_in"))
      (node (ref "U3") (pin "15") (pinfunction "GND_15") (pintype "passive"))
      (node (ref "U4") (pin "1") (pinfunction "GND_1") (pintype "passive"))
      (node (ref "USB1") (pin "4") (pinfunction "GND_4") (pintype "passive"))
      (node (ref "USB1") (pin "5") (pinfunction "SHELL_5") (pintype "passive"))
      (node (ref "USB1") (pin "6") (pinfunction "SHELL_6") (pintype "passive"))
      (node (ref "USB2") (pin "4") (pinfunction "GND_4") (pintype "passive"))
      (node (ref "USB2") (pin "5") (pinfunction "SHELL_5") (pintype "passive"))
      (node (ref "USB2") (pin "6") (pinfunction "SHELL_6") (pintype "passive"))
    )
    (net (code "45") (name "Net-(D2-Pad1)") (class "Default")
      (node (ref "D2") (pin "1") (pinfunction "1_1") (pintype "passive"))
      (node (ref "R4") (pin "2") (pinfunction "2_2") (pintype "passive"))
    )
    (net (code "46") (name "Net-(D3-Pad1)") (class "Default")
      (node (ref "D3") (pin "1") (pinfunction "1_1") (pintype "passive"))
      (node (ref "R6") (pin "2") (pinfunction "2_2") (pintype "passive"))
    )
    (net (code "47") (name "Net-(D4-Pad1)") (class "Default")
      (node (ref "D4") (pin "1") (pinfunction "1_1") (pintype "passive"))
      (node (ref "R7") (pin "1") (pinfunction "1_1") (pintype "passive"))
    )
    (net (code "48") (name "Net-(J1-VUSB)") (class "Default")
      (node (ref "F7") (pin "1") (pinfunction "1_1") (pintype "passive"))
      (node (ref "J1") (pin "1") (pinfunction "VUSB_1") (pintype "passive"))
    )
    (net (code "49") (name "Net-(LED1-Pad1)") (class "Default")
      (node (ref "LED1") (pin "1") (pinfunction "1_1") (pintype "passive"))
      (node (ref "R10") (pin "1") (pinfunction "1_1") (pintype "passive"))
    )
    (net (code "50") (name "Net-(Q1-G)") (class "Default")
      (node (ref "Q1") (pin "1") (pinfunction "G_1") (pintype "passive"))
      (node (ref "R26") (pin "1") (pinfunction "1_1") (pintype "passive"))
    )
    (net (code "51") (name "Net-(U1-V3)") (class "Default")
      (node (ref "C2") (pin "2") (pinfunction "2_2") (pintype "passive"))
      (node (ref "U1") (pin "5") (pinfunction "V3_5") (pintype "passive"))
    )
    (net (code "52") (name "Net-(U2-BOOT0)") (class "Default")
      (node (ref "R12") (pin "2") (pinfunction "2_2") (pintype "passive"))
      (node (ref "U2") (pin "44") (pinfunction "BOOT0_44") (pintype "input"))
    )
    (net (code "53") (name "Net-(U2-PB2{slash}BOOT1)") (class "Default")
      (node (ref "R9") (pin "1") (pinfunction "1_1") (pintype "passive"))
      (node (ref "U2") (pin "20") (pinfunction "PB2/BOOT1_20") (pintype "bidirectional"))
    )
    (net (code "54") (name "Net-(U3-DVDD)") (class "Default")
      (node (ref "F4") (pin "1") (pinfunction "1_1") (pintype "passive"))
      (node (ref "U3") (pin "16") (pinfunction "DVDD_16") (pintype "passive"))
    )
    (net (code "55") (name "Net-(USB1-VBUS)") (class "Default")
      (node (ref "C15") (pin "2") (pinfunction "2_2") (pintype "passive"))
      (node (ref "F5") (pin "2") (pinfunction "2_2") (pintype "passive"))
      (node (ref "USB1") (pin "1") (pinfunction "VBUS_1") (pintype "passive"))
    )
    (net (code "56") (name "Net-(USB2-VBUS)") (class "Default")
      (node (ref "C22") (pin "2") (pinfunction "2_2") (pintype "passive"))
      (node (ref "F6") (pin "2") (pinfunction "2_2") (pintype "passive"))
      (node (ref "USB2") (pin "1") (pinfunction "VBUS_1") (pintype "passive"))
    )
    (net (code "57") (name "Net-(Y3-0)") (class "Default")
      (node (ref "C17") (pin "2") (pinfunction "2_2") (pintype "passive"))
      (node (ref "R14") (pin "1") (pinfunction "1_1") (pintype "passive"))
      (node (ref "Y3") (pin "1") (pinfunction "0_1") (pintype "passive"))
    )
    (net (code "58") (name "TTL_VCC") (class "Default")
      (node (ref "C1") (pin "2") (pinfunction "2_2") (pintype "passive"))
      (node (ref "F1") (pin "2") (pinfunction "2_2") (pintype "passive"))
      (node (ref "P1") (pin "4") (pinfunction "4_4") (pintype "passive"))
      (node (ref "R4") (pin "1") (pinfunction "1_1") (pintype "passive"))
      (node (ref "R6") (pin "1") (pinfunction "1_1") (pintype "passive"))
      (node (ref "U1") (pin "19") (pinfunction "VCC_19") (pintype "passive"))
    )
    (net (code "59") (name "USBVCC") (class "Default")
      (node (ref "F7") (pin "2") (pinfunction "2_2") (pintype "passive"))
      (node (ref "Q1") (pin "3") (pinfunction "D_3") (pintype "passive"))
      (node (ref "R17") (pin "2") (pinfunction "2_2") (pintype "passive"))
    )
    (net (code "60") (name "USBVDD") (class "Default")
      (node (ref "C24") (pin "1") (pinfunction "1_1") (pintype "passive"))
      (node (ref "EC2") (pin "1") (pinfunction "1_1") (pintype "passive"))
      (node (ref "EC3") (pin "1") (pinfunction "1_1") (pintype "passive"))
      (node (ref "F1") (pin "1") (pinfunction "1_1") (pintype "passive"))
      (node (ref "F2") (pin "1") (pinfunction "1_1") (pintype "passive"))
      (node (ref "F5") (pin "1") (pinfunction "1_1") (pintype "passive"))
      (node (ref "F6") (pin "1") (pinfunction "1_1") (pintype "passive"))
      (node (ref "R15") (pin "2") (pinfunction "2_2") (pintype "passive"))
      (node (ref "U4") (pin "3") (pinfunction "IN_3") (pintype "passive"))
    )
    (net (code "61") (name "VCC_3V3") (class "Default")
      (node (ref "C20") (pin "1") (pinfunction "1_1") (pintype "passive"))
      (node (ref "C23") (pin "1") (pinfunction "1_1") (pintype "passive"))
      (node (ref "C25") (pin "1") (pinfunction "1_1") (pintype "passive"))
      (node (ref "C27") (pin "1") (pinfunction "1_1") (pintype "passive"))
      (node (ref "C28") (pin "1") (pinfunction "1_1") (pintype "passive"))
      (node (ref "C29") (pin "1") (pinfunction "1_1") (pintype "passive"))
      (node (ref "C3") (pin "1") (pinfunction "1_1") (pintype "passive"))
      (node (ref "C30") (pin "1") (pinfunction "1_1") (pintype "passive"))
      (node (ref "C6") (pin "1") (pinfunction "1_1") (pintype "passive"))
      (node (ref "ISP1") (pin "4") (pinfunction "4_4") (pintype "passive"))
      (node (ref "OUT1") (pin "1") (pinfunction "1_1") (pintype "passive"))
      (node (ref "R13") (pin "2") (pinfunction "2_2") (pintype "passive"))
      (node (ref "R27") (pin "2") (pinfunction "2_2") (pintype "passive"))
      (node (ref "R7") (pin "2") (pinfunction "2_2") (pintype "passive"))
      (node (ref "U2") (pin "1") (pinfunction "VBAT_1") (pintype "power_in"))
      (node (ref "U2") (pin "24") (pinfunction "VDD_1_24") (pintype "power_in"))
      (node (ref "U2") (pin "36") (pinfunction "VDD_2_36") (pintype "power_in"))
      (node (ref "U2") (pin "48") (pinfunction "VDD_3_48") (pintype "power_in"))
      (node (ref "U2") (pin "9") (pinfunction "VDDA_9") (pintype "power_in"))
      (node (ref "U4") (pin "2") (pinfunction "OUT_2") (pintype "passive"))
    )
    (net (code "62") (name "VCC_5V") (class "Default")
      (node (ref "C26") (pin "2") (pinfunction "2_2") (pintype "passive"))
      (node (ref "EC5") (pin "1") (pinfunction "1_1") (pintype "passive"))
      (node (ref "F2") (pin "2") (pinfunction "2_2") (pintype "passive"))
      (node (ref "JA1") (pin "1") (pinfunction "1_1") (pintype "power_in"))
      (node (ref "Q1") (pin "2") (pinfunction "S_2") (pintype "passive"))
      (node (ref "R22") (pin "2") (pinfunction "2_2") (pintype "passive"))
      (node (ref "U3") (pin "23") (pinfunction "V5_23") (pintype "passive"))
    )
    (net (code "63") (name "unconnected-(J1-ID-Pad4)") (class "Default")
      (node (ref "J1") (pin "4") (pinfunction "ID_4") (pintype "passive+no_connect"))
    )
    (net (code "64") (name "unconnected-(U1-ACT#-Pad2)") (class "Default")
      (node (ref "U1") (pin "2") (pinfunction "ACT#_2") (pintype "passive"))
    )
    (net (code "65") (name "unconnected-(U1-CKO-Pad1)") (class "Default")
      (node (ref "U1") (pin "1") (pinfunction "CKO_1") (pintype "passive"))
    )
    (net (code "66") (name "unconnected-(U1-CTS#-Pad11)") (class "Default")
      (node (ref "U1") (pin "11") (pinfunction "CTS#_11") (pintype "passive"))
    )
    (net (code "67") (name "unconnected-(U1-DCD#-Pad14)") (class "Default")
      (node (ref "U1") (pin "14") (pinfunction "DCD#_14") (pintype "passive"))
    )
    (net (code "68") (name "unconnected-(U1-DSR#-Pad12)") (class "Default")
      (node (ref "U1") (pin "12") (pinfunction "DSR#_12") (pintype "passive"))
    )
    (net (code "69") (name "unconnected-(U1-DTR#-Pad15)") (class "Default")
      (node (ref "U1") (pin "15") (pinfunction "DTR#_15") (pintype "passive"))
    )
    (net (code "70") (name "unconnected-(U1-NC-Pad17)") (class "Default")
      (node (ref "U1") (pin "17") (pinfunction "NC_17") (pintype "passive"))
    )
    (net (code "71") (name "unconnected-(U1-NOS#-Pad20)") (class "Default")
      (node (ref "U1") (pin "20") (pinfunction "NOS#_20") (pintype "passive"))
    )
    (net (code "72") (name "unconnected-(U1-R232-Pad18)") (class "Default")
      (node (ref "U1") (pin "18") (pinfunction "R232_18") (pintype "passive"))
    )
    (net (code "73") (name "unconnected-(U1-RI#-Pad13)") (class "Default")
      (node (ref "U1") (pin "13") (pinfunction "RI#_13") (pintype "passive"))
    )
    (net (code "74") (name "unconnected-(U1-RTS#-Pad16)") (class "Default")
      (node (ref "U1") (pin "16") (pinfunction "RTS#_16") (pintype "passive"))
    )
    (net (code "75") (name "unconnected-(U2-PA8-Pad29)") (class "Default")
      (node (ref "U2") (pin "29") (pinfunction "PA8_29") (pintype "bidirectional+no_connect"))
    )
    (net (code "76") (name "unconnected-(U2-PA15{slash}JTDI-Pad38)") (class "Default")
      (node (ref "U2") (pin "38") (pinfunction "PA15/JTDI_38") (pintype "bidirectional+no_connect"))
    )
    (net (code "77") (name "unconnected-(U2-PB3{slash}JTDO-Pad39)") (class "Default")
      (node (ref "U2") (pin "39") (pinfunction "PB3/JTDO_39") (pintype "bidirectional+no_connect"))
    )
    (net (code "78") (name "unconnected-(U2-PB4{slash}JNTRST-Pad40)") (class "Default")
      (node (ref "U2") (pin "40") (pinfunction "PB4/JNTRST_40") (pintype "bidirectional+no_connect"))
    )
    (net (code "79") (name "unconnected-(U2-PB5-Pad41)") (class "Default")
      (node (ref "U2") (pin "41") (pinfunction "PB5_41") (pintype "bidirectional+no_connect"))
    )
    (net (code "80") (name "unconnected-(U2-PB6-Pad42)") (class "Default")
      (node (ref "U2") (pin "42") (pinfunction "PB6_42") (pintype "bidirectional+no_connect"))
    )
    (net (code "81") (name "unconnected-(U2-PB7-Pad43)") (class "Default")
      (node (ref "U2") (pin "43") (pinfunction "PB7_43") (pintype "bidirectional+no_connect"))
    )
    (net (code "82") (name "unconnected-(U2-PB8-Pad45)") (class "Default")
      (node (ref "U2") (pin "45") (pinfunction "PB8_45") (pintype "bidirectional+no_connect"))
    )
    (net (code "83") (name "unconnected-(U2-PB9-Pad46)") (class "Default")
      (node (ref "U2") (pin "46") (pinfunction "PB9_46") (pintype "bidirectional+no_connect"))
    )
    (net (code "84") (name "unconnected-(U2-PB10-Pad21)") (class "Default")
      (node (ref "U2") (pin "21") (pinfunction "PB10_21") (pintype "bidirectional+no_connect"))
    )
    (net (code "85") (name "unconnected-(U2-PB11-Pad22)") (class "Default")
      (node (ref "U2") (pin "22") (pinfunction "PB11_22") (pintype "bidirectional+no_connect"))
    )
    (net (code "86") (name "unconnected-(U2-PC13-TAMPER-RTC-Pad2)") (class "Default")
      (node (ref "U2") (pin "2") (pinfunction "PC13-TAMPER-RTC_2") (pintype "bidirectional+no_connect"))
    )
    (net (code "87") (name "unconnected-(U2-PC14-OSC32_IN-Pad3)") (class "Default")
      (node (ref "U2") (pin "3") (pinfunction "PC14-OSC32_IN_3") (pintype "bidirectional+no_connect"))
    )
    (net (code "88") (name "unconnected-(U2-PC15-OSC32_OUT-Pad4)") (class "Default")
      (node (ref "U2") (pin "4") (pinfunction "PC15-OSC32_OUT_4") (pintype "bidirectional+no_connect"))
    )
    (net (code "89") (name "unconnected-(U3-OVCUR2#-Pad19)") (class "Default")
      (node (ref "U3") (pin "19") (pinfunction "OVCUR2#_19") (pintype "passive"))
    )
    (net (code "90") (name "unconnected-(U3-PWREN1#-Pad22)") (class "Default")
      (node (ref "U3") (pin "22") (pinfunction "PWREN1#_22") (pintype "passive"))
    )
    (net (code "91") (name "unconnected-(U3-PWREN2#-Pad20)") (class "Default")
      (node (ref "U3") (pin "20") (pinfunction "PWREN2#_20") (pintype "passive"))
    )
    (net (code "92") (name "unconnected-(U3-TEST{slash}SCL-Pad14)") (class "Default")
      (node (ref "U3") (pin "14") (pinfunction "TEST/SCL_14") (pintype "passive"))
    )
  )
)
